# envelope.net
KiCad netlist of a schematic drawn in Altium Designer
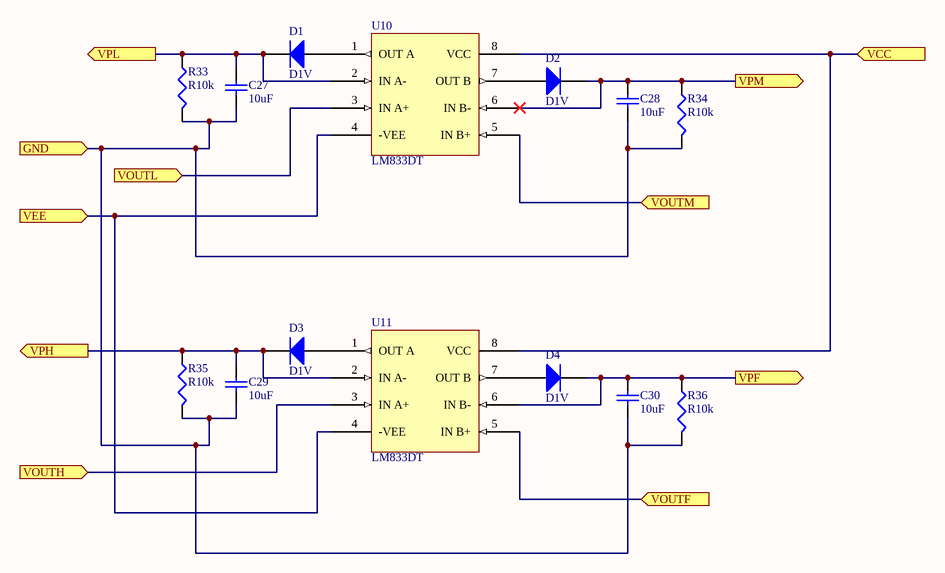
[diagram p0: envelope.SchDoc]

(export (version "E")
  (design (tool "Eeschema 10.0.6"))
  (components
    (comp (ref "C27")
      (value "10uF")
      (footprint "C0603")
      (description "10 uF Surface Mount Capacitor")
      (fields
        (field (name "MANUFACTURER") "Yageo")
        (field (name "MANUFACTURER PART NUMBER") "CC0603KRX5R5BB106")
      )
      (libsource (lib "Capstone Libraries") (part "C10uF"))
    )
    (comp (ref "C28")
      (value "10uF")
      (footprint "C0603")
      (description "10 uF Surface Mount Capacitor")
      (fields
        (field (name "MANUFACTURER") "Yageo")
        (field (name "MANUFACTURER PART NUMBER") "CC0603KRX5R5BB106")
      )
      (libsource (lib "Capstone Libraries") (part "C10uF"))
    )
    (comp (ref "C29")
      (value "10uF")
      (footprint "C0603")
      (description "10 uF Surface Mount Capacitor")
      (fields
        (field (name "MANUFACTURER") "Yageo")
        (field (name "MANUFACTURER PART NUMBER") "CC0603KRX5R5BB106")
      )
      (libsource (lib "Capstone Libraries") (part "C10uF"))
    )
    (comp (ref "C30")
      (value "10uF")
      (footprint "C0603")
      (description "10 uF Surface Mount Capacitor")
      (fields
        (field (name "MANUFACTURER") "Yageo")
        (field (name "MANUFACTURER PART NUMBER") "CC0603KRX5R5BB106")
      )
      (libsource (lib "Capstone Libraries") (part "C10uF"))
    )
    (comp (ref "D1")
      (value "D1V")
      (footprint "D1206")
      (description "Standard 1V Diode")
      (fields
        (field (name "MANUFACTURER") "Bourns Inc.")
        (field (name "MANUFACTURER PART NUMBER") "CD1206-S01575")
      )
      (libsource (lib "Capstone Libraries") (part "D1V"))
    )
    (comp (ref "D2")
      (value "D1V")
      (footprint "D1206")
      (description "Standard 1V Diode")
      (fields
        (field (name "MANUFACTURER") "Bourns Inc.")
        (field (name "MANUFACTURER PART NUMBER") "CD1206-S01575")
      )
      (libsource (lib "Capstone Libraries") (part "D1V"))
    )
    (comp (ref "D3")
      (value "D1V")
      (footprint "D1206")
      (description "Standard 1V Diode")
      (fields
        (field (name "MANUFACTURER") "Bourns Inc.")
        (field (name "MANUFACTURER PART NUMBER") "CD1206-S01575")
      )
      (libsource (lib "Capstone Libraries") (part "D1V"))
    )
    (comp (ref "D4")
      (value "D1V")
      (footprint "D1206")
      (description "Standard 1V Diode")
      (fields
        (field (name "MANUFACTURER") "Bourns Inc.")
        (field (name "MANUFACTURER PART NUMBER") "CD1206-S01575")
      )
      (libsource (lib "Capstone Libraries") (part "D1V"))
    )
    (comp (ref "R33")
      (value "R10k")
      (footprint "R0603")
      (description "10k Ohms Surface Mount Resistor")
      (fields
        (field (name "MANUFACTURER") "Yageo")
        (field (name "MANUFACTURER PART NUMBER") "RC0603FR-0710KL")
      )
      (libsource (lib "Capstone Libraries") (part "R10k"))
    )
    (comp (ref "R34")
      (value "R10k")
      (footprint "R0603")
      (description "10k Ohms Surface Mount Resistor")
      (fields
        (field (name "MANUFACTURER") "Yageo")
        (field (name "MANUFACTURER PART NUMBER") "RC0603FR-0710KL")
      )
      (libsource (lib "Capstone Libraries") (part "R10k"))
    )
    (comp (ref "R35")
      (value "R10k")
      (footprint "R0603")
      (description "10k Ohms Surface Mount Resistor")
      (fields
        (field (name "MANUFACTURER") "Yageo")
        (field (name "MANUFACTURER PART NUMBER") "RC0603FR-0710KL")
      )
      (libsource (lib "Capstone Libraries") (part "R10k"))
    )
    (comp (ref "R36")
      (value "R10k")
      (footprint "R0603")
      (description "10k Ohms Surface Mount Resistor")
      (fields
        (field (name "MANUFACTURER") "Yageo")
        (field (name "MANUFACTURER PART NUMBER") "RC0603FR-0710KL")
      )
      (libsource (lib "Capstone Libraries") (part "R10k"))
    )
    (comp (ref "U10")
      (value "LM833DT")
      (footprint "soic8")
      (description "IC Dual Audio Amplifier")
      (fields (field (name "MANUFACTURER") "STMicroelectronics"))
      (libsource (lib "Capstone Libraries") (part "LM833DT"))
    )
    (comp (ref "U11")
      (value "LM833DT")
      (footprint "soic8")
      (description "IC Dual Audio Amplifier")
      (fields (field (name "MANUFACTURER") "STMicroelectronics"))
      (libsource (lib "Capstone Libraries") (part "LM833DT"))
    )
  )
  (nets
    (net (code "1") (name "/GND") (class "Default")
      (node (ref "C27") (pin "2") (pinfunction "2_2") (pintype "passive"))
      (node (ref "C28") (pin "2") (pinfunction "2_2") (pintype "passive"))
      (node (ref "C29") (pin "2") (pinfunction "2_2") (pintype "passive"))
      (node (ref "C30") (pin "2") (pinfunction "2_2") (pintype "passive"))
      (node (ref "R33") (pin "2") (pinfunction "2_2") (pintype "passive"))
      (node (ref "R34") (pin "2") (pinfunction "2_2") (pintype "passive"))
      (node (ref "R35") (pin "2") (pinfunction "2_2") (pintype "passive"))
      (node (ref "R36") (pin "2") (pinfunction "2_2") (pintype "passive"))
    )
    (net (code "2") (name "/VCC") (class "Default")
      (node (ref "U10") (pin "8") (pinfunction "VCC_8") (pintype "passive"))
      (node (ref "U11") (pin "8") (pinfunction "VCC_8") (pintype "passive"))
    )
    (net (code "3") (name "/VEE") (class "Default")
      (node (ref "U10") (pin "4") (pinfunction "-VEE_4") (pintype "passive"))
      (node (ref "U11") (pin "4") (pinfunction "-VEE_4") (pintype "passive"))
    )
    (net (code "4") (name "/VOUTF") (class "Default")
      (node (ref "U11") (pin "5") (pinfunction "IN_B+_5") (pintype "input"))
    )
    (net (code "5") (name "/VOUTH") (class "Default")
      (node (ref "U11") (pin "3") (pinfunction "IN_A+_3") (pintype "input"))
    )
    (net (code "6") (name "/VOUTL") (class "Default")
      (node (ref "U10") (pin "3") (pinfunction "IN_A+_3") (pintype "input"))
    )
    (net (code "7") (name "/VOUTM") (class "Default")
      (node (ref "U10") (pin "5") (pinfunction "IN_B+_5") (pintype "input"))
    )
    (net (code "8") (name "/VPF") (class "Default")
      (node (ref "C30") (pin "1") (pinfunction "1_1") (pintype "passive"))
      (node (ref "D4") (pin "2") (pinfunction "K_2") (pintype "passive"))
      (node (ref "R36") (pin "1") (pinfunction "1_1") (pintype "passive"))
      (node (ref "U11") (pin "6") (pinfunction "IN_B-_6") (pintype "input"))
    )
    (net (code "9") (name "/VPH") (class "Default")
      (node (ref "C29") (pin "1") (pinfunction "1_1") (pintype "passive"))
      (node (ref "D3") (pin "2") (pinfunction "K_2") (pintype "passive"))
      (node (ref "R35") (pin "1") (pinfunction "1_1") (pintype "passive"))
      (node (ref "U11") (pin "2") (pinfunction "IN_A-_2") (pintype "input"))
    )
    (net (code "10") (name "/VPL") (class "Default")
      (node (ref "C27") (pin "1") (pinfunction "1_1") (pintype "passive"))
      (node (ref "D1") (pin "2") (pinfunction "K_2") (pintype "passive"))
      (node (ref "R33") (pin "1") (pinfunction "1_1") (pintype "passive"))
      (node (ref "U10") (pin "2") (pinfunction "IN_A-_2") (pintype "input"))
    )
    (net (code "11") (name "/VPM") (class "Default")
      (node (ref "C28") (pin "1") (pinfunction "1_1") (pintype "passive"))
      (node (ref "D2") (pin "2") (pinfunction "K_2") (pintype "passive"))
      (node (ref "R34") (pin "1") (pinfunction "1_1") (pintype "passive"))
      (node (ref "U10") (pin "6") (pinfunction "IN_B-_6") (pintype "input"))
    )
    (net (code "12") (name "Net-(D1-A)") (class "Default")
      (node (ref "D1") (pin "1") (pinfunction "A_1") (pintype "passive"))
      (node (ref "U10") (pin "1") (pinfunction "OUT_A_1") (pintype "output"))
    )
    (net (code "13") (name "Net-(D2-A)") (class "Default")
      (node (ref "D2") (pin "1") (pinfunction "A_1") (pintype "passive"))
      (node (ref "U10") (pin "7") (pinfunction "OUT_B_7") (pintype "output"))
    )
    (net (code "14") (name "Net-(D3-A)") (class "Default")
      (node (ref "D3") (pin "1") (pinfunction "A_1") (pintype "passive"))
      (node (ref "U11") (pin "1") (pinfunction "OUT_A_1") (pintype "output"))
    )
    (net (code "15") (name "Net-(D4-A)") (class "Default")
      (node (ref "D4") (pin "1") (pinfunction "A_1") (pintype "passive"))
      (node (ref "U11") (pin "7") (pinfunction "OUT_B_7") (pintype "output"))
    )
  )
)
